# IZU2023_board2_ver7_2.net
KiCad netlist of a schematic drawn in EAGLE
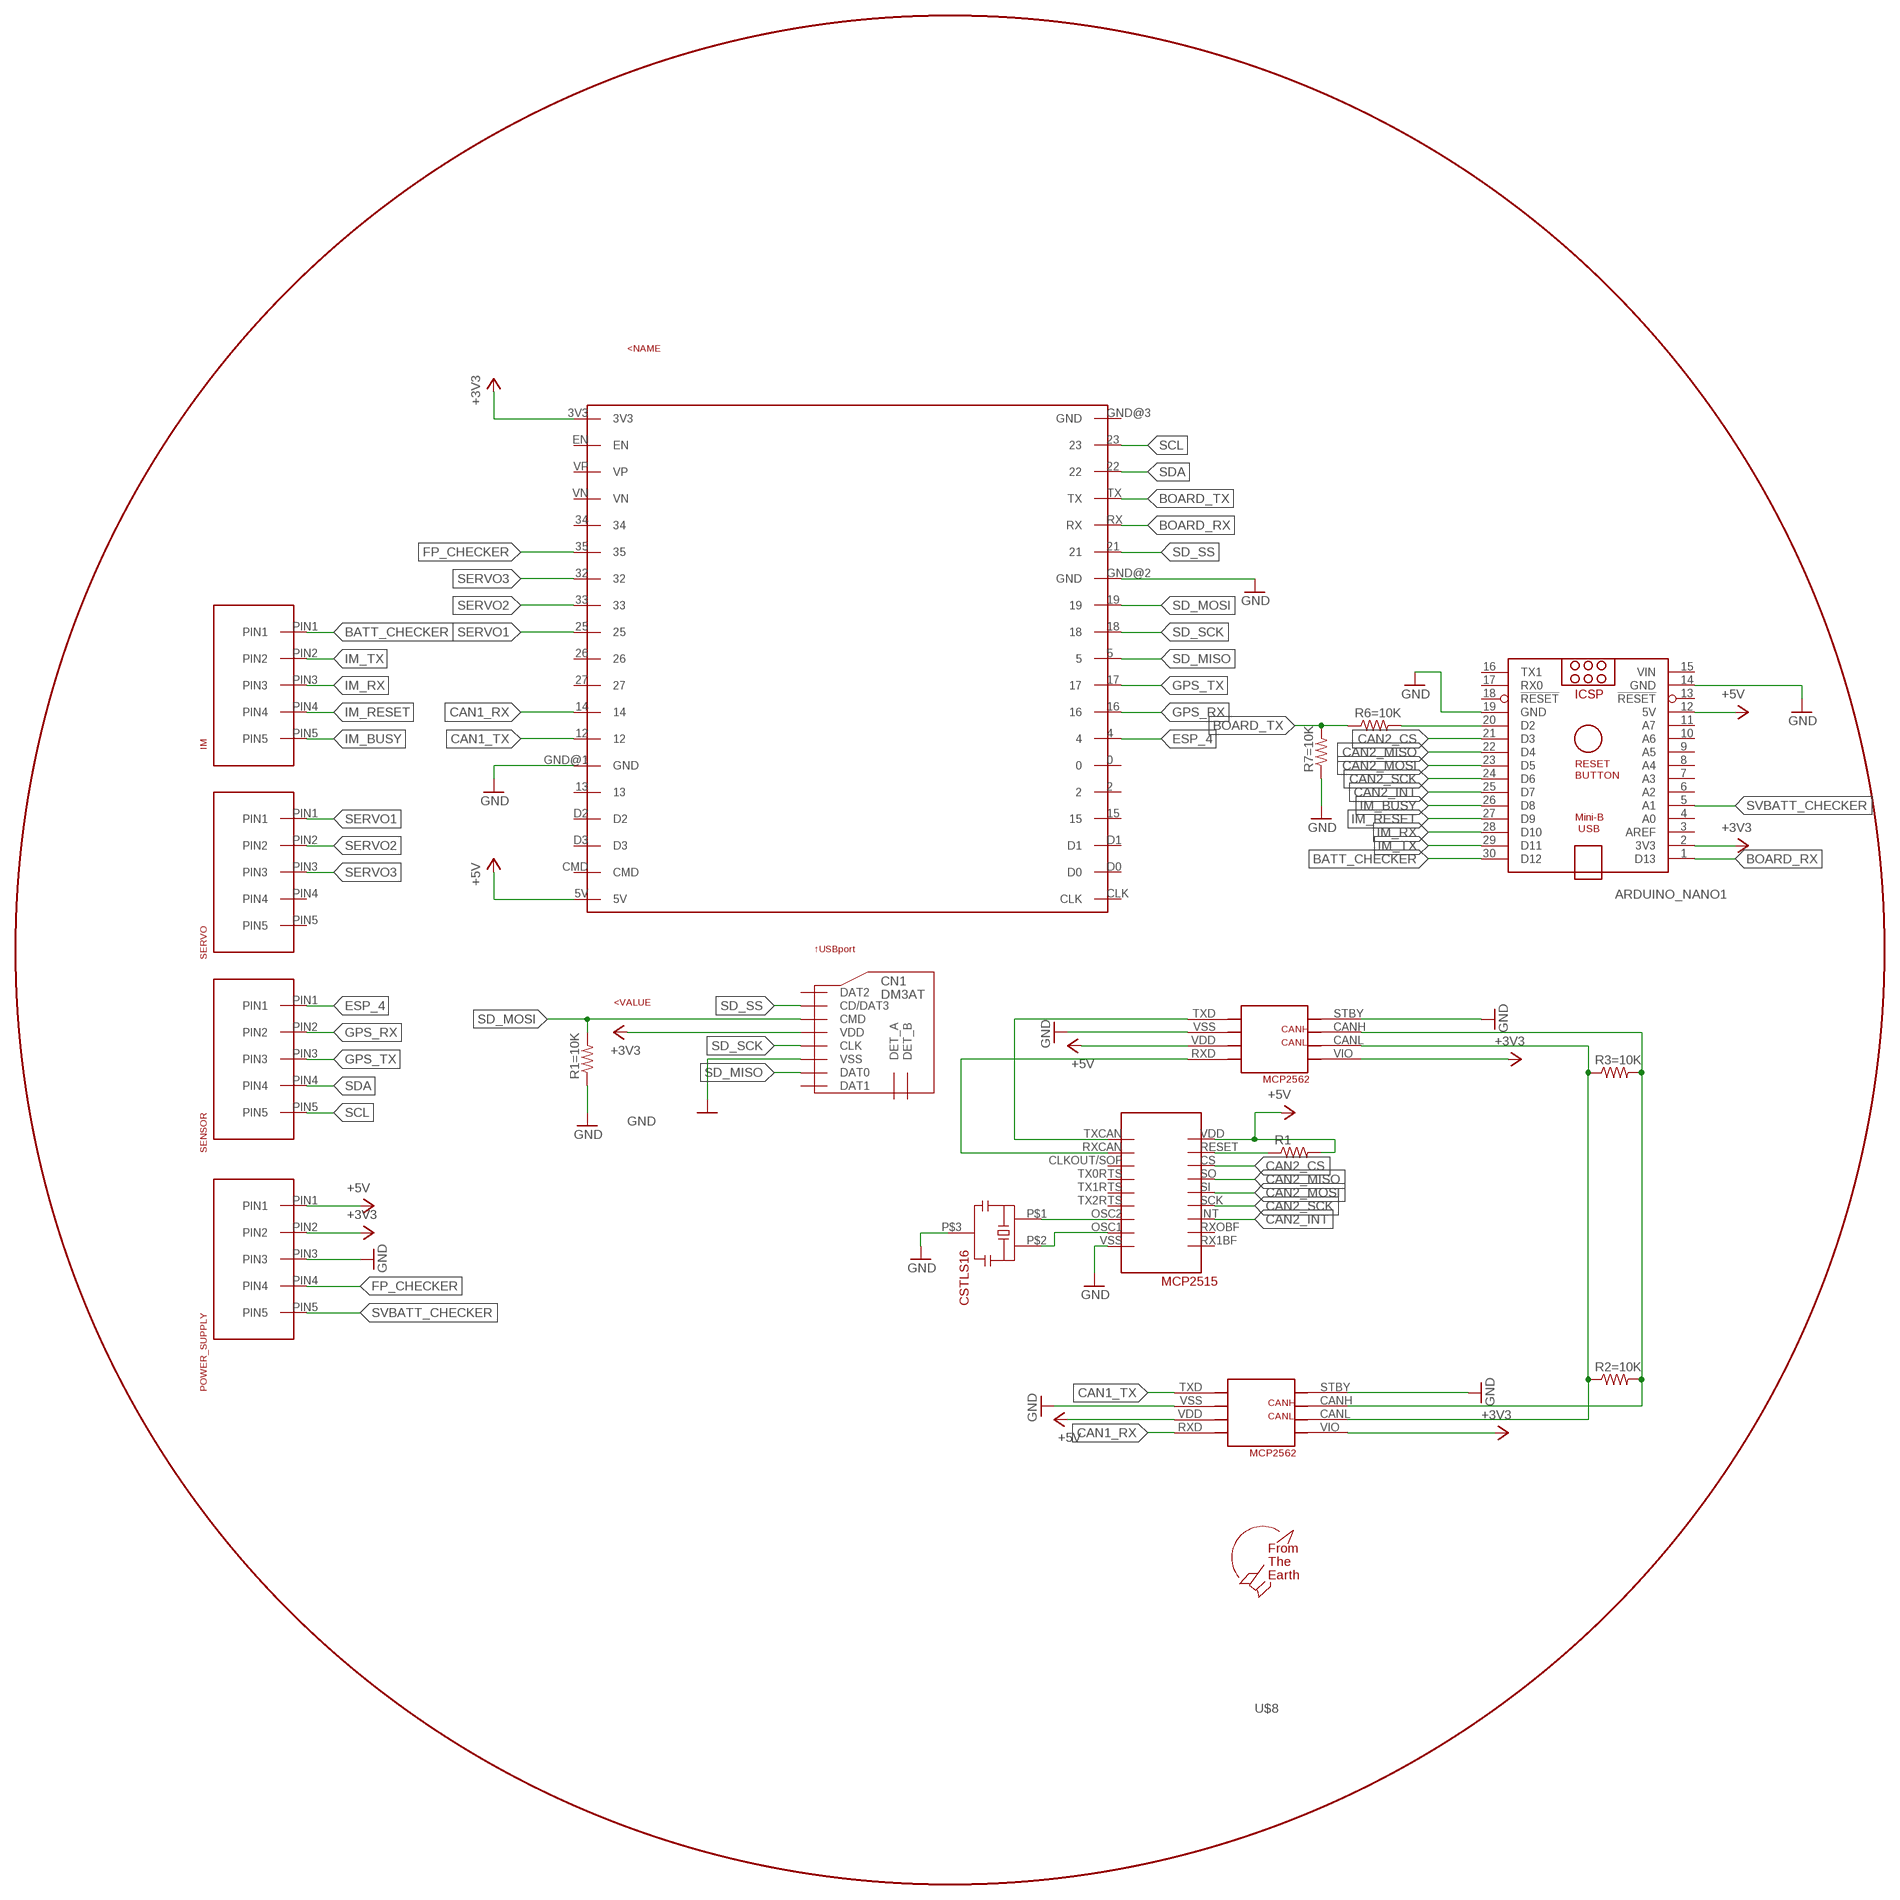
[diagram p0: schematic, sheet 1]

(export (version "E")
  (design (tool "Eeschema 10.0.6"))
  (components
    (comp (ref "ARDUINO_NANO1")
      (value "ARDUINO_NANO")
      (footprint "eagle-import:ARDUINO_NANO")
      (libsource (lib "eagle-import") (part "ARDUINO_NANO"))
    )
    (comp (ref "CN1")
      (value "DM3AT")
      (footprint "eagle-import:DM3AT")
      (libsource (lib "eagle-import") (part "DM3AT"))
    )
    (comp (ref "IM")
      (value "5PIN")
      (footprint "eagle-import:5PIN")
      (libsource (lib "eagle-import") (part "5PIN"))
    )
    (comp (ref "POWER_SUPPLY")
      (value "5PIN")
      (footprint "eagle-import:5PIN")
      (libsource (lib "eagle-import") (part "5PIN"))
    )
    (comp (ref "R1")
      (value "R-US_0204/7")
      (footprint "eagle-import:0204_7")
      (libsource (lib "eagle-import") (part "R-US_0204/7"))
    )
    (comp (ref "R1=10K")
      (value "R-US_0204/7")
      (footprint "eagle-import:0204_7")
      (libsource (lib "eagle-import") (part "R-US_0204/7"))
    )
    (comp (ref "R2=10K")
      (value "R-US_0204/7")
      (footprint "eagle-import:0204_7")
      (libsource (lib "eagle-import") (part "R-US_0204/7"))
    )
    (comp (ref "R3=10K")
      (value "R-US_0204/7")
      (footprint "eagle-import:0204_7")
      (libsource (lib "eagle-import") (part "R-US_0204/7"))
    )
    (comp (ref "R6=10K")
      (value "R-US_0204/7")
      (footprint "eagle-import:0204_7")
      (libsource (lib "eagle-import") (part "R-US_0204/7"))
    )
    (comp (ref "R7=10K")
      (value "R-US_0204/7")
      (footprint "eagle-import:0204_7")
      (libsource (lib "eagle-import") (part "R-US_0204/7"))
    )
    (comp (ref "SENSOR")
      (value "5PIN")
      (footprint "eagle-import:5PIN")
      (libsource (lib "eagle-import") (part "5PIN"))
    )
    (comp (ref "SERVO")
      (value "5PIN")
      (footprint "eagle-import:5PIN")
      (libsource (lib "eagle-import") (part "5PIN"))
    )
    (comp (ref "U$1")
      (value "ESP32-DEVKITC")
      (footprint "eagle-import:ESP32-DEVKITC")
      (libsource (lib "eagle-import") (part "ESP32-DEVKITC"))
    )
    (comp (ref "U$2")
      (value "MCP2515")
      (footprint "eagle-import:MCP2515")
      (libsource (lib "eagle-import") (part "MCP2515"))
    )
    (comp (ref "U$3")
      (value "MCP2562")
      (footprint "eagle-import:MCP2562")
      (libsource (lib "eagle-import") (part "MCP2562"))
    )
    (comp (ref "U$4")
      (value "MCP2562")
      (footprint "eagle-import:MCP2562")
      (libsource (lib "eagle-import") (part "MCP2562"))
    )
    (comp (ref "U$5")
      (value "CSTLS16")
      (footprint "eagle-import:CSTLS16")
      (libsource (lib "eagle-import") (part "CSTLS16"))
    )
    (comp (ref "U$8")
      (value "F.T.E.LOGO")
      (footprint "eagle-import:LOGO")
      (libsource (lib "eagle-import") (part "F.T.E.LOGO"))
    )
  )
  (nets
    (net (code "1") (name "+3V3") (class "Default")
      (node (ref "ARDUINO_NANO1") (pin "2") (pinfunction "3V3_2") (pintype "output"))
      (node (ref "CN1") (pin "VDD") (pinfunction "VDD_VDD") (pintype "bidirectional"))
      (node (ref "POWER_SUPPLY") (pin "PIN2") (pinfunction "PIN2_PIN2") (pintype "bidirectional"))
      (node (ref "U$1") (pin "3V3") (pinfunction "3V3_3V3") (pintype "bidirectional"))
      (node (ref "U$3") (pin "VIO") (pinfunction "VIO_VIO") (pintype "bidirectional"))
      (node (ref "U$4") (pin "VIO") (pinfunction "VIO_VIO") (pintype "bidirectional"))
    )
    (net (code "2") (name "+5V") (class "Default")
      (node (ref "ARDUINO_NANO1") (pin "12") (pinfunction "5V_12") (pintype "power_in"))
      (node (ref "POWER_SUPPLY") (pin "PIN1") (pinfunction "PIN1_PIN1") (pintype "bidirectional"))
      (node (ref "R1") (pin "2") (pinfunction "2_2") (pintype "passive"))
      (node (ref "U$1") (pin "5V") (pinfunction "5V_5V") (pintype "bidirectional"))
      (node (ref "U$2") (pin "VDD") (pinfunction "VDD_VDD") (pintype "bidirectional"))
      (node (ref "U$3") (pin "VDD") (pinfunction "VDD_VDD") (pintype "bidirectional"))
      (node (ref "U$4") (pin "VDD") (pinfunction "VDD_VDD") (pintype "bidirectional"))
    )
    (net (code "3") (name "/VIN") (class "Default")
      (node (ref "ARDUINO_NANO1") (pin "15") (pinfunction "VIN_15") (pintype "power_in"))
    )
    (net (code "4") (name "BATT_CHECKER") (class "Default")
      (node (ref "ARDUINO_NANO1") (pin "30") (pinfunction "D12_30") (pintype "bidirectional"))
      (node (ref "IM") (pin "PIN1") (pinfunction "PIN1_PIN1") (pintype "bidirectional"))
    )
    (net (code "5") (name "BOARD_RX") (class "Default")
      (node (ref "ARDUINO_NANO1") (pin "1") (pinfunction "D13_1") (pintype "bidirectional"))
      (node (ref "U$1") (pin "RX") (pinfunction "RX_RX") (pintype "bidirectional"))
    )
    (net (code "6") (name "BOARD_TX") (class "Default")
      (node (ref "R6=10K") (pin "1") (pinfunction "1_1") (pintype "passive"))
      (node (ref "R7=10K") (pin "2") (pinfunction "2_2") (pintype "passive"))
      (node (ref "U$1") (pin "TX") (pinfunction "TX_TX") (pintype "bidirectional"))
    )
    (net (code "7") (name "CAN1_RX") (class "Default")
      (node (ref "U$1") (pin "14") (pinfunction "14_14") (pintype "bidirectional"))
      (node (ref "U$3") (pin "RXD") (pinfunction "RXD_RXD") (pintype "bidirectional"))
    )
    (net (code "8") (name "CAN1_TX") (class "Default")
      (node (ref "U$1") (pin "12") (pinfunction "12_12") (pintype "bidirectional"))
      (node (ref "U$3") (pin "TXD") (pinfunction "TXD_TXD") (pintype "bidirectional"))
    )
    (net (code "9") (name "CAN2_CS") (class "Default")
      (node (ref "ARDUINO_NANO1") (pin "21") (pinfunction "D3_21") (pintype "bidirectional"))
      (node (ref "U$2") (pin "CS") (pinfunction "CS_CS") (pintype "bidirectional"))
    )
    (net (code "10") (name "CAN2_INT") (class "Default")
      (node (ref "ARDUINO_NANO1") (pin "25") (pinfunction "D7_25") (pintype "bidirectional"))
      (node (ref "U$2") (pin "INT") (pinfunction "INT_INT") (pintype "bidirectional"))
    )
    (net (code "11") (name "CAN2_MISO") (class "Default")
      (node (ref "ARDUINO_NANO1") (pin "22") (pinfunction "D4_22") (pintype "bidirectional"))
      (node (ref "U$2") (pin "SO") (pinfunction "SO_SO") (pintype "bidirectional"))
    )
    (net (code "12") (name "CAN2_MOSI") (class "Default")
      (node (ref "ARDUINO_NANO1") (pin "23") (pinfunction "D5_23") (pintype "bidirectional"))
      (node (ref "U$2") (pin "SI") (pinfunction "SI_SI") (pintype "bidirectional"))
    )
    (net (code "13") (name "CAN2_SCK") (class "Default")
      (node (ref "ARDUINO_NANO1") (pin "24") (pinfunction "D6_24") (pintype "bidirectional"))
      (node (ref "U$2") (pin "SCK") (pinfunction "SCK_SCK") (pintype "bidirectional"))
    )
    (net (code "14") (name "ESP_4") (class "Default")
      (node (ref "SENSOR") (pin "PIN1") (pinfunction "PIN1_PIN1") (pintype "bidirectional"))
      (node (ref "U$1") (pin "4") (pinfunction "4_4") (pintype "bidirectional"))
    )
    (net (code "15") (name "FP_CHECKER") (class "Default")
      (node (ref "POWER_SUPPLY") (pin "PIN4") (pinfunction "PIN4_PIN4") (pintype "bidirectional"))
      (node (ref "U$1") (pin "35") (pinfunction "35_35") (pintype "bidirectional"))
    )
    (net (code "16") (name "GND") (class "Default")
      (node (ref "ARDUINO_NANO1") (pin "14") (pinfunction "GND_14") (pintype "power_in"))
      (node (ref "ARDUINO_NANO1") (pin "19") (pinfunction "GND_19") (pintype "power_in"))
      (node (ref "CN1") (pin "VSS") (pinfunction "VSS_VSS") (pintype "bidirectional"))
      (node (ref "POWER_SUPPLY") (pin "PIN3") (pinfunction "PIN3_PIN3") (pintype "bidirectional"))
      (node (ref "R1=10K") (pin "1") (pinfunction "1_1") (pintype "passive"))
      (node (ref "R7=10K") (pin "1") (pinfunction "1_1") (pintype "passive"))
      (node (ref "U$1") (pin "GND@1") (pinfunction "GND_GND@1") (pintype "bidirectional"))
      (node (ref "U$1") (pin "GND@2") (pinfunction "GND_GND@2") (pintype "bidirectional"))
      (node (ref "U$2") (pin "VSS") (pinfunction "VSS_VSS") (pintype "bidirectional"))
      (node (ref "U$3") (pin "STBY") (pinfunction "STBY_STBY") (pintype "bidirectional"))
      (node (ref "U$3") (pin "VSS") (pinfunction "VSS_VSS") (pintype "bidirectional"))
      (node (ref "U$4") (pin "STBY") (pinfunction "STBY_STBY") (pintype "bidirectional"))
      (node (ref "U$4") (pin "VSS") (pinfunction "VSS_VSS") (pintype "bidirectional"))
      (node (ref "U$5") (pin "P$3") (pinfunction "P$3_P$3") (pintype "bidirectional"))
    )
    (net (code "17") (name "GPS_RX") (class "Default")
      (node (ref "SENSOR") (pin "PIN2") (pinfunction "PIN2_PIN2") (pintype "bidirectional"))
      (node (ref "U$1") (pin "16") (pinfunction "16_16") (pintype "bidirectional"))
    )
    (net (code "18") (name "GPS_TX") (class "Default")
      (node (ref "SENSOR") (pin "PIN3") (pinfunction "PIN3_PIN3") (pintype "bidirectional"))
      (node (ref "U$1") (pin "17") (pinfunction "17_17") (pintype "bidirectional"))
    )
    (net (code "19") (name "IM_BUSY") (class "Default")
      (node (ref "ARDUINO_NANO1") (pin "26") (pinfunction "D8_26") (pintype "bidirectional"))
      (node (ref "IM") (pin "PIN5") (pinfunction "PIN5_PIN5") (pintype "bidirectional"))
    )
    (net (code "20") (name "IM_RESET") (class "Default")
      (node (ref "ARDUINO_NANO1") (pin "27") (pinfunction "D9_27") (pintype "bidirectional"))
      (node (ref "IM") (pin "PIN4") (pinfunction "PIN4_PIN4") (pintype "bidirectional"))
    )
    (net (code "21") (name "IM_RX") (class "Default")
      (node (ref "ARDUINO_NANO1") (pin "28") (pinfunction "D10_28") (pintype "bidirectional"))
      (node (ref "IM") (pin "PIN3") (pinfunction "PIN3_PIN3") (pintype "bidirectional"))
    )
    (net (code "22") (name "IM_TX") (class "Default")
      (node (ref "ARDUINO_NANO1") (pin "29") (pinfunction "D11_29") (pintype "bidirectional"))
      (node (ref "IM") (pin "PIN2") (pinfunction "PIN2_PIN2") (pintype "bidirectional"))
    )
    (net (code "23") (name "Net-(ARDUINO_NANO1-D2)") (class "Default")
      (node (ref "ARDUINO_NANO1") (pin "20") (pinfunction "D2_20") (pintype "bidirectional"))
      (node (ref "R6=10K") (pin "2") (pinfunction "2_2") (pintype "passive"))
    )
    (net (code "24") (name "Net-(R1-Pad1)") (class "Default")
      (node (ref "R1") (pin "1") (pinfunction "1_1") (pintype "passive"))
      (node (ref "U$2") (pin "RESET") (pinfunction "RESET_RESET") (pintype "bidirectional"))
    )
    (net (code "25") (name "Net-(R2=10K-Pad1)") (class "Default")
      (node (ref "R2=10K") (pin "1") (pinfunction "1_1") (pintype "passive"))
      (node (ref "R3=10K") (pin "1") (pinfunction "1_1") (pintype "passive"))
      (node (ref "U$3") (pin "CANL") (pinfunction "CANL_CANL") (pintype "bidirectional"))
      (node (ref "U$4") (pin "CANL") (pinfunction "CANL_CANL") (pintype "bidirectional"))
    )
    (net (code "26") (name "Net-(R2=10K-Pad2)") (class "Default")
      (node (ref "R2=10K") (pin "2") (pinfunction "2_2") (pintype "passive"))
      (node (ref "R3=10K") (pin "2") (pinfunction "2_2") (pintype "passive"))
      (node (ref "U$3") (pin "CANH") (pinfunction "CANH_CANH") (pintype "bidirectional"))
      (node (ref "U$4") (pin "CANH") (pinfunction "CANH_CANH") (pintype "bidirectional"))
    )
    (net (code "27") (name "Net-(U$2-PadOSC1)") (class "Default")
      (node (ref "U$2") (pin "OSC1") (pinfunction "OSC1_OSC1") (pintype "bidirectional"))
      (node (ref "U$5") (pin "P$2") (pinfunction "P$2_P$2") (pintype "bidirectional"))
    )
    (net (code "28") (name "Net-(U$2-PadOSC2)") (class "Default")
      (node (ref "U$2") (pin "OSC2") (pinfunction "OSC2_OSC2") (pintype "bidirectional"))
      (node (ref "U$5") (pin "P$1") (pinfunction "P$1_P$1") (pintype "bidirectional"))
    )
    (net (code "29") (name "Net-(U$2-PadRXCAN)") (class "Default")
      (node (ref "U$2") (pin "RXCAN") (pinfunction "RXCAN_RXCAN") (pintype "bidirectional"))
      (node (ref "U$4") (pin "RXD") (pinfunction "RXD_RXD") (pintype "bidirectional"))
    )
    (net (code "30") (name "Net-(U$2-PadTXCAN)") (class "Default")
      (node (ref "U$2") (pin "TXCAN") (pinfunction "TXCAN_TXCAN") (pintype "bidirectional"))
      (node (ref "U$4") (pin "TXD") (pinfunction "TXD_TXD") (pintype "bidirectional"))
    )
    (net (code "31") (name "SCL") (class "Default")
      (node (ref "SENSOR") (pin "PIN5") (pinfunction "PIN5_PIN5") (pintype "bidirectional"))
      (node (ref "U$1") (pin "23") (pinfunction "23_23") (pintype "bidirectional"))
    )
    (net (code "32") (name "SDA") (class "Default")
      (node (ref "SENSOR") (pin "PIN4") (pinfunction "PIN4_PIN4") (pintype "bidirectional"))
      (node (ref "U$1") (pin "22") (pinfunction "22_22") (pintype "bidirectional"))
    )
    (net (code "33") (name "SD_MISO") (class "Default")
      (node (ref "CN1") (pin "DAT0") (pinfunction "DAT0_DAT0") (pintype "bidirectional"))
      (node (ref "U$1") (pin "5") (pinfunction "5_5") (pintype "bidirectional"))
    )
    (net (code "34") (name "SD_MOSI") (class "Default")
      (node (ref "CN1") (pin "CMD") (pinfunction "CMD_CMD") (pintype "bidirectional"))
      (node (ref "R1=10K") (pin "2") (pinfunction "2_2") (pintype "passive"))
      (node (ref "U$1") (pin "19") (pinfunction "19_19") (pintype "bidirectional"))
    )
    (net (code "35") (name "SD_SCK") (class "Default")
      (node (ref "CN1") (pin "CLK") (pinfunction "CLK_CLK") (pintype "bidirectional"))
      (node (ref "U$1") (pin "18") (pinfunction "18_18") (pintype "bidirectional"))
    )
    (net (code "36") (name "SD_SS") (class "Default")
      (node (ref "CN1") (pin "CD/DAT3") (pinfunction "CD/DAT3_CD/DAT3") (pintype "bidirectional"))
      (node (ref "U$1") (pin "21") (pinfunction "21_21") (pintype "bidirectional"))
    )
    (net (code "37") (name "SERVO1") (class "Default")
      (node (ref "SERVO") (pin "PIN1") (pinfunction "PIN1_PIN1") (pintype "bidirectional"))
      (node (ref "U$1") (pin "25") (pinfunction "25_25") (pintype "bidirectional"))
    )
    (net (code "38") (name "SERVO2") (class "Default")
      (node (ref "SERVO") (pin "PIN2") (pinfunction "PIN2_PIN2") (pintype "bidirectional"))
      (node (ref "U$1") (pin "33") (pinfunction "33_33") (pintype "bidirectional"))
    )
    (net (code "39") (name "SERVO3") (class "Default")
      (node (ref "SERVO") (pin "PIN3") (pinfunction "PIN3_PIN3") (pintype "bidirectional"))
      (node (ref "U$1") (pin "32") (pinfunction "32_32") (pintype "bidirectional"))
    )
    (net (code "40") (name "SVBATT_CHECKER") (class "Default")
      (node (ref "ARDUINO_NANO1") (pin "5") (pinfunction "A1_5") (pintype "bidirectional"))
      (node (ref "POWER_SUPPLY") (pin "PIN5") (pinfunction "PIN5_PIN5") (pintype "bidirectional"))
    )
    (net (code "41") (name "unconnected-(ARDUINO_NANO1-A0-Pad4)") (class "Default")
      (node (ref "ARDUINO_NANO1") (pin "4") (pinfunction "A0_4") (pintype "bidirectional"))
    )
    (net (code "42") (name "unconnected-(ARDUINO_NANO1-A2-Pad6)") (class "Default")
      (node (ref "ARDUINO_NANO1") (pin "6") (pinfunction "A2_6") (pintype "bidirectional"))
    )
    (net (code "43") (name "unconnected-(ARDUINO_NANO1-A3-Pad7)") (class "Default")
      (node (ref "ARDUINO_NANO1") (pin "7") (pinfunction "A3_7") (pintype "bidirectional"))
    )
    (net (code "44") (name "unconnected-(ARDUINO_NANO1-A4-Pad8)") (class "Default")
      (node (ref "ARDUINO_NANO1") (pin "8") (pinfunction "A4_8") (pintype "bidirectional"))
    )
    (net (code "45") (name "unconnected-(ARDUINO_NANO1-A5-Pad9)") (class "Default")
      (node (ref "ARDUINO_NANO1") (pin "9") (pinfunction "A5_9") (pintype "bidirectional"))
    )
    (net (code "46") (name "unconnected-(ARDUINO_NANO1-A6-Pad10)") (class "Default")
      (node (ref "ARDUINO_NANO1") (pin "10") (pinfunction "A6_10") (pintype "bidirectional"))
    )
    (net (code "47") (name "unconnected-(ARDUINO_NANO1-A7-Pad11)") (class "Default")
      (node (ref "ARDUINO_NANO1") (pin "11") (pinfunction "A7_11") (pintype "bidirectional"))
    )
    (net (code "48") (name "unconnected-(ARDUINO_NANO1-AREF-Pad3)") (class "Default")
      (node (ref "ARDUINO_NANO1") (pin "3") (pinfunction "AREF_3") (pintype "input"))
    )
    (net (code "49") (name "unconnected-(ARDUINO_NANO1-RX0-Pad17)") (class "Default")
      (node (ref "ARDUINO_NANO1") (pin "17") (pinfunction "RX0_17") (pintype "bidirectional"))
    )
    (net (code "50") (name "unconnected-(ARDUINO_NANO1-TX1-Pad16)") (class "Default")
      (node (ref "ARDUINO_NANO1") (pin "16") (pinfunction "TX1_16") (pintype "bidirectional"))
    )
    (net (code "51") (name "unconnected-(ARDUINO_NANO1-~{RESET}-Pad13)") (class "Default")
      (node (ref "ARDUINO_NANO1") (pin "13") (pinfunction "~{RESET}_13") (pintype "input"))
    )
    (net (code "52") (name "unconnected-(ARDUINO_NANO1-~{RESET}-Pad18)") (class "Default")
      (node (ref "ARDUINO_NANO1") (pin "18") (pinfunction "~{RESET}_18") (pintype "input"))
    )
    (net (code "53") (name "unconnected-(CN1-PadDAT1)") (class "Default")
      (node (ref "CN1") (pin "DAT1") (pinfunction "DAT1_DAT1") (pintype "bidirectional"))
    )
    (net (code "54") (name "unconnected-(CN1-PadDAT2)") (class "Default")
      (node (ref "CN1") (pin "DAT2") (pinfunction "DAT2_DAT2") (pintype "bidirectional"))
    )
    (net (code "55") (name "unconnected-(CN1-PadDET_A)") (class "Default")
      (node (ref "CN1") (pin "DET_A") (pinfunction "DET_A_DET_A") (pintype "bidirectional"))
    )
    (net (code "56") (name "unconnected-(CN1-PadDET_B)") (class "Default")
      (node (ref "CN1") (pin "DET_B") (pinfunction "DET_B_DET_B") (pintype "bidirectional"))
    )
    (net (code "57") (name "unconnected-(SERVO-PadPIN4)") (class "Default")
      (node (ref "SERVO") (pin "PIN4") (pinfunction "PIN4_PIN4") (pintype "bidirectional"))
    )
    (net (code "58") (name "unconnected-(SERVO-PadPIN5)") (class "Default")
      (node (ref "SERVO") (pin "PIN5") (pinfunction "PIN5_PIN5") (pintype "bidirectional"))
    )
    (net (code "59") (name "unconnected-(U$1-GND-PadGND@3)") (class "Default")
      (node (ref "U$1") (pin "GND@3") (pinfunction "GND_GND@3") (pintype "bidirectional"))
    )
    (net (code "60") (name "unconnected-(U$1-Pad0)") (class "Default")
      (node (ref "U$1") (pin "0") (pinfunction "0_0") (pintype "bidirectional"))
    )
    (net (code "61") (name "unconnected-(U$1-Pad2)") (class "Default")
      (node (ref "U$1") (pin "2") (pinfunction "2_2") (pintype "bidirectional"))
    )
    (net (code "62") (name "unconnected-(U$1-Pad13)") (class "Default")
      (node (ref "U$1") (pin "13") (pinfunction "13_13") (pintype "bidirectional"))
    )
    (net (code "63") (name "unconnected-(U$1-Pad15)") (class "Default")
      (node (ref "U$1") (pin "15") (pinfunction "15_15") (pintype "bidirectional"))
    )
    (net (code "64") (name "unconnected-(U$1-Pad26)") (class "Default")
      (node (ref "U$1") (pin "26") (pinfunction "26_26") (pintype "bidirectional"))
    )
    (net (code "65") (name "unconnected-(U$1-Pad27)") (class "Default")
      (node (ref "U$1") (pin "27") (pinfunction "27_27") (pintype "bidirectional"))
    )
    (net (code "66") (name "unconnected-(U$1-Pad34)") (class "Default")
      (node (ref "U$1") (pin "34") (pinfunction "34_34") (pintype "bidirectional"))
    )
    (net (code "67") (name "unconnected-(U$1-PadCLK)") (class "Default")
      (node (ref "U$1") (pin "CLK") (pinfunction "CLK_CLK") (pintype "bidirectional"))
    )
    (net (code "68") (name "unconnected-(U$1-PadCMD)") (class "Default")
      (node (ref "U$1") (pin "CMD") (pinfunction "CMD_CMD") (pintype "bidirectional"))
    )
    (net (code "69") (name "unconnected-(U$1-PadD0)") (class "Default")
      (node (ref "U$1") (pin "D0") (pinfunction "D0_D0") (pintype "bidirectional"))
    )
    (net (code "70") (name "unconnected-(U$1-PadD1)") (class "Default")
      (node (ref "U$1") (pin "D1") (pinfunction "D1_D1") (pintype "bidirectional"))
    )
    (net (code "71") (name "unconnected-(U$1-PadD2)") (class "Default")
      (node (ref "U$1") (pin "D2") (pinfunction "D2_D2") (pintype "bidirectional"))
    )
    (net (code "72") (name "unconnected-(U$1-PadD3)") (class "Default")
      (node (ref "U$1") (pin "D3") (pinfunction "D3_D3") (pintype "bidirectional"))
    )
    (net (code "73") (name "unconnected-(U$1-PadEN)") (class "Default")
      (node (ref "U$1") (pin "EN") (pinfunction "EN_EN") (pintype "bidirectional"))
    )
    (net (code "74") (name "unconnected-(U$1-PadVN)") (class "Default")
      (node (ref "U$1") (pin "VN") (pinfunction "VN_VN") (pintype "bidirectional"))
    )
    (net (code "75") (name "unconnected-(U$1-PadVP)") (class "Default")
      (node (ref "U$1") (pin "VP") (pinfunction "VP_VP") (pintype "bidirectional"))
    )
    (net (code "76") (name "unconnected-(U$2-PadCLKOUT{slash}SOF)") (class "Default")
      (node (ref "U$2") (pin "CLKOUT/SOF") (pinfunction "CLKOUT/SOF_CLKOUT/SOF") (pintype "bidirectional"))
    )
    (net (code "77") (name "unconnected-(U$2-PadRX1BF)") (class "Default")
      (node (ref "U$2") (pin "RX1BF") (pinfunction "RX1BF_RX1BF") (pintype "bidirectional"))
    )
    (net (code "78") (name "unconnected-(U$2-PadTX0RTS)") (class "Default")
      (node (ref "U$2") (pin "TX0RTS") (pinfunction "TX0RTS_TX0RTS") (pintype "bidirectional"))
    )
    (net (code "79") (name "unconnected-(U$2-PadTX1RTS)") (class "Default")
      (node (ref "U$2") (pin "TX1RTS") (pinfunction "TX1RTS_TX1RTS") (pintype "bidirectional"))
    )
    (net (code "80") (name "unconnected-(U$2-PadTX2RTS)") (class "Default")
      (node (ref "U$2") (pin "TX2RTS") (pinfunction "TX2RTS_TX2RTS") (pintype "bidirectional"))
    )
    (net (code "81") (name "unconnected-(U$2-RX0BF-PadRXOBF)") (class "Default")
      (node (ref "U$2") (pin "RXOBF") (pinfunction "RX0BF_RXOBF") (pintype "bidirectional"))
    )
  )
)
